# MIC.net
KiCad netlist of a schematic drawn in Altium Designer
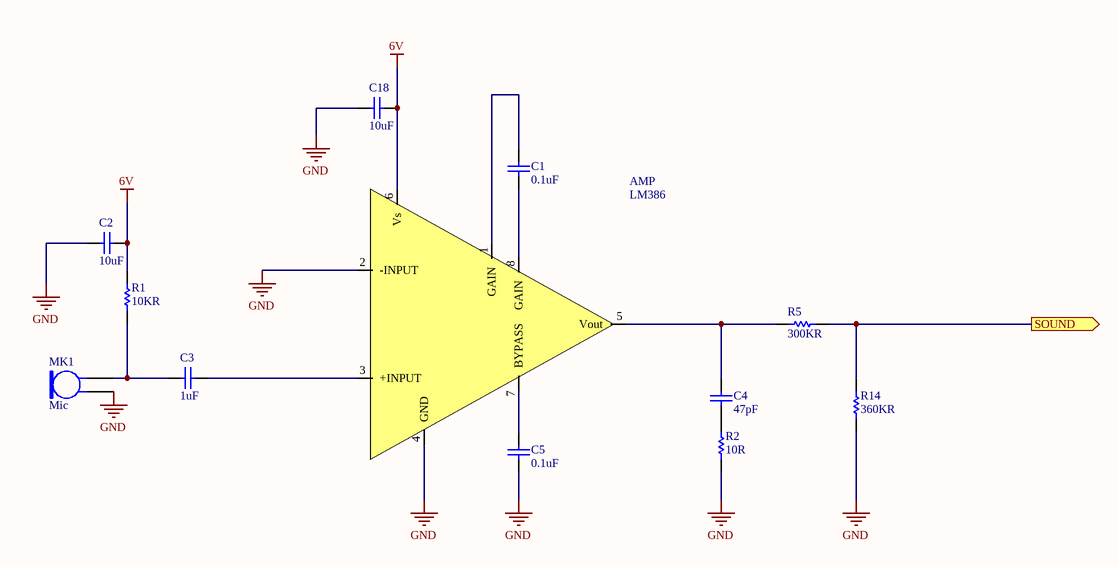
[diagram p0: MIC.SchDoc]

(export (version "E")
  (design (tool "Eeschema 10.0.6"))
  (components
    (comp (ref "AMP") (value "LM386") (footprint "Ampli") (libsource (lib "SCHLIB_Autobot") (part "LM386")))
    (comp (ref "C1")
      (value "0.1uF")
      (footprint "CAPC1608N")
      (description "Capacitor")
      (fields (field (name "PUBLISHER") "Altium Limited"))
      (libsource (lib "Miscellaneous Devices") (part "Cap"))
    )
    (comp (ref "C2")
      (value "10uF")
      (footprint "CAPC1608N")
      (description "Capacitor")
      (fields (field (name "PUBLISHER") "Altium Limited"))
      (libsource (lib "Miscellaneous Devices") (part "Cap"))
    )
    (comp (ref "C3")
      (value "1uF")
      (footprint "CAPC1608N")
      (description "Capacitor")
      (fields (field (name "PUBLISHER") "Altium Limited"))
      (libsource (lib "Miscellaneous Devices") (part "Cap"))
    )
    (comp (ref "C4")
      (value "47pF")
      (footprint "CAPC1608N")
      (description "Capacitor")
      (fields (field (name "PUBLISHER") "Altium Limited"))
      (libsource (lib "Miscellaneous Devices") (part "Cap"))
    )
    (comp (ref "C5")
      (value "0.1uF")
      (footprint "CAPC1608N")
      (description "Capacitor")
      (fields (field (name "PUBLISHER") "Altium Limited"))
      (libsource (lib "Miscellaneous Devices") (part "Cap"))
    )
    (comp (ref "C18")
      (value "10uF")
      (footprint "CAPC1608N")
      (description "Capacitor")
      (fields (field (name "PUBLISHER") "Altium Limited"))
      (libsource (lib "Miscellaneous Devices") (part "Cap"))
    )
    (comp (ref "MK1")
      (value "Mic")
      (footprint "BORNIER")
      (description "Microphone")
      (fields (field (name "PUBLISHER") "Altium Limited"))
      (libsource (lib "Miscellaneous Devices") (part "Mic2"))
    )
    (comp (ref "R1")
      (value "10KR")
      (footprint "RESC1608N")
      (description "Resistor")
      (fields (field (name "PUBLISHER") "Altium Limited"))
      (libsource (lib "Miscellaneous Devices") (part "Res1"))
    )
    (comp (ref "R2")
      (value "10R")
      (footprint "RESC1608N")
      (description "Resistor")
      (fields (field (name "PUBLISHER") "Altium Limited"))
      (libsource (lib "Miscellaneous Devices") (part "Res1"))
    )
    (comp (ref "R5")
      (value "300KR")
      (footprint "RESC1608N")
      (description "Resistor")
      (fields (field (name "PUBLISHER") "Altium Limited"))
      (libsource (lib "Miscellaneous Devices") (part "Res1"))
    )
    (comp (ref "R14")
      (value "360KR")
      (footprint "RESC1608N")
      (description "Resistor")
      (fields (field (name "PUBLISHER") "Altium Limited"))
      (libsource (lib "Miscellaneous Devices") (part "Res1"))
    )
  )
  (nets
    (net (code "1") (name "/SOUND") (class "Default")
      (node (ref "R14") (pin "1") (pinfunction "1_1") (pintype "passive"))
      (node (ref "R5") (pin "2") (pinfunction "2_2") (pintype "passive"))
    )
    (net (code "2") (name "6V") (class "Default")
      (node (ref "AMP") (pin "6") (pinfunction "Vs_6") (pintype "passive"))
      (node (ref "C18") (pin "2") (pinfunction "2_2") (pintype "passive"))
      (node (ref "C2") (pin "2") (pinfunction "2_2") (pintype "passive"))
      (node (ref "R1") (pin "1") (pinfunction "1_1") (pintype "passive"))
    )
    (net (code "3") (name "GND") (class "Default")
      (node (ref "AMP") (pin "2") (pinfunction "-INPUT_2") (pintype "passive"))
      (node (ref "AMP") (pin "4") (pinfunction "GND_4") (pintype "passive"))
      (node (ref "C18") (pin "1") (pinfunction "1_1") (pintype "passive"))
      (node (ref "C2") (pin "1") (pinfunction "1_1") (pintype "passive"))
      (node (ref "C5") (pin "2") (pinfunction "2_2") (pintype "passive"))
      (node (ref "MK1") (pin "1") (pinfunction "1_1") (pintype "passive"))
      (node (ref "R14") (pin "2") (pinfunction "2_2") (pintype "passive"))
      (node (ref "R2") (pin "2") (pinfunction "2_2") (pintype "passive"))
    )
    (net (code "4") (name "Net-(AMP-+INPUT)") (class "Default")
      (node (ref "AMP") (pin "3") (pinfunction "+INPUT_3") (pintype "passive"))
      (node (ref "C3") (pin "1") (pinfunction "1_1") (pintype "passive"))
    )
    (net (code "5") (name "Net-(AMP-BYPASS)") (class "Default")
      (node (ref "AMP") (pin "7") (pinfunction "BYPASS_7") (pintype "passive"))
      (node (ref "C5") (pin "1") (pinfunction "1_1") (pintype "passive"))
    )
    (net (code "6") (name "Net-(AMP-GAIN-Pad1)") (class "Default")
      (node (ref "AMP") (pin "1") (pinfunction "GAIN_1") (pintype "passive"))
      (node (ref "C1") (pin "1") (pinfunction "1_1") (pintype "passive"))
    )
    (net (code "7") (name "Net-(AMP-GAIN-Pad8)") (class "Default")
      (node (ref "AMP") (pin "8") (pinfunction "GAIN_8") (pintype "passive"))
      (node (ref "C1") (pin "2") (pinfunction "2_2") (pintype "passive"))
    )
    (net (code "8") (name "Net-(AMP-Vout)") (class "Default")
      (node (ref "AMP") (pin "5") (pinfunction "Vout_5") (pintype "passive"))
      (node (ref "C4") (pin "1") (pinfunction "1_1") (pintype "passive"))
      (node (ref "R5") (pin "1") (pinfunction "1_1") (pintype "passive"))
    )
    (net (code "9") (name "Net-(C3-Pad2)") (class "Default")
      (node (ref "C3") (pin "2") (pinfunction "2_2") (pintype "passive"))
      (node (ref "MK1") (pin "2") (pinfunction "2_2") (pintype "passive"))
      (node (ref "R1") (pin "2") (pinfunction "2_2") (pintype "passive"))
    )
    (net (code "10") (name "Net-(C4-Pad2)") (class "Default")
      (node (ref "C4") (pin "2") (pinfunction "2_2") (pintype "passive"))
      (node (ref "R2") (pin "1") (pinfunction "1_1") (pintype "passive"))
    )
  )
)
